# common_emitter-punto_di_lavoro.net
KiCad netlist of a schematic drawn in EAGLE
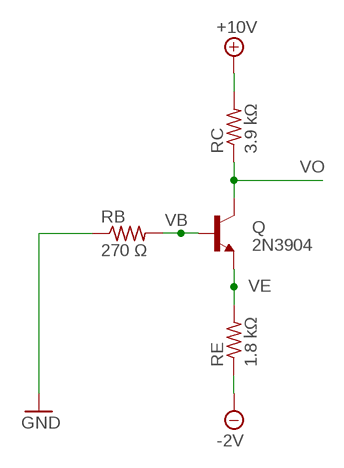
[diagram p0: schematic, sheet 1]

(export (version "E")
  (design (tool "Eeschema 10.0.6"))
  (components
    (comp (ref "Q")
      (value "2N3904")
      (footprint "eagle-import:TO92")
      (libsource (lib "eagle-import") (part "2N3904"))
    )
    (comp (ref "RB")
      (value "270 Ω")
      (footprint "eagle-import:0204_5")
      (libsource (lib "eagle-import") (part "R-US_0204/5"))
    )
    (comp (ref "RC")
      (value "3.9 kΩ")
      (footprint "eagle-import:0204_5")
      (libsource (lib "eagle-import") (part "R-US_0204/5"))
    )
    (comp (ref "RE")
      (value "1.8 kΩ")
      (footprint "eagle-import:0204_5")
      (libsource (lib "eagle-import") (part "R-US_0204/5"))
    )
  )
  (nets
    (net (code "1") (name "+10V") (class "Default")
      (node (ref "RC") (pin "2") (pinfunction "2_2") (pintype "passive"))
    )
    (net (code "2") (name "-10V") (class "Default")
      (node (ref "RE") (pin "1") (pinfunction "1_1") (pintype "passive"))
    )
    (net (code "3") (name "/VB") (class "Default")
      (node (ref "Q") (pin "2") (pinfunction "B_2") (pintype "passive"))
      (node (ref "RB") (pin "2") (pinfunction "2_2") (pintype "passive"))
    )
    (net (code "4") (name "/VE") (class "Default")
      (node (ref "Q") (pin "3") (pinfunction "E_3") (pintype "passive"))
      (node (ref "RE") (pin "2") (pinfunction "2_2") (pintype "passive"))
    )
    (net (code "5") (name "/VO") (class "Default")
      (node (ref "Q") (pin "1") (pinfunction "C_1") (pintype "passive"))
      (node (ref "RC") (pin "1") (pinfunction "1_1") (pintype "passive"))
    )
    (net (code "6") (name "GND") (class "Default")
      (node (ref "RB") (pin "1") (pinfunction "1_1") (pintype "passive"))
    )
  )
)
